# face_board.net
KiCad netlist of a schematic drawn in Altium Designer
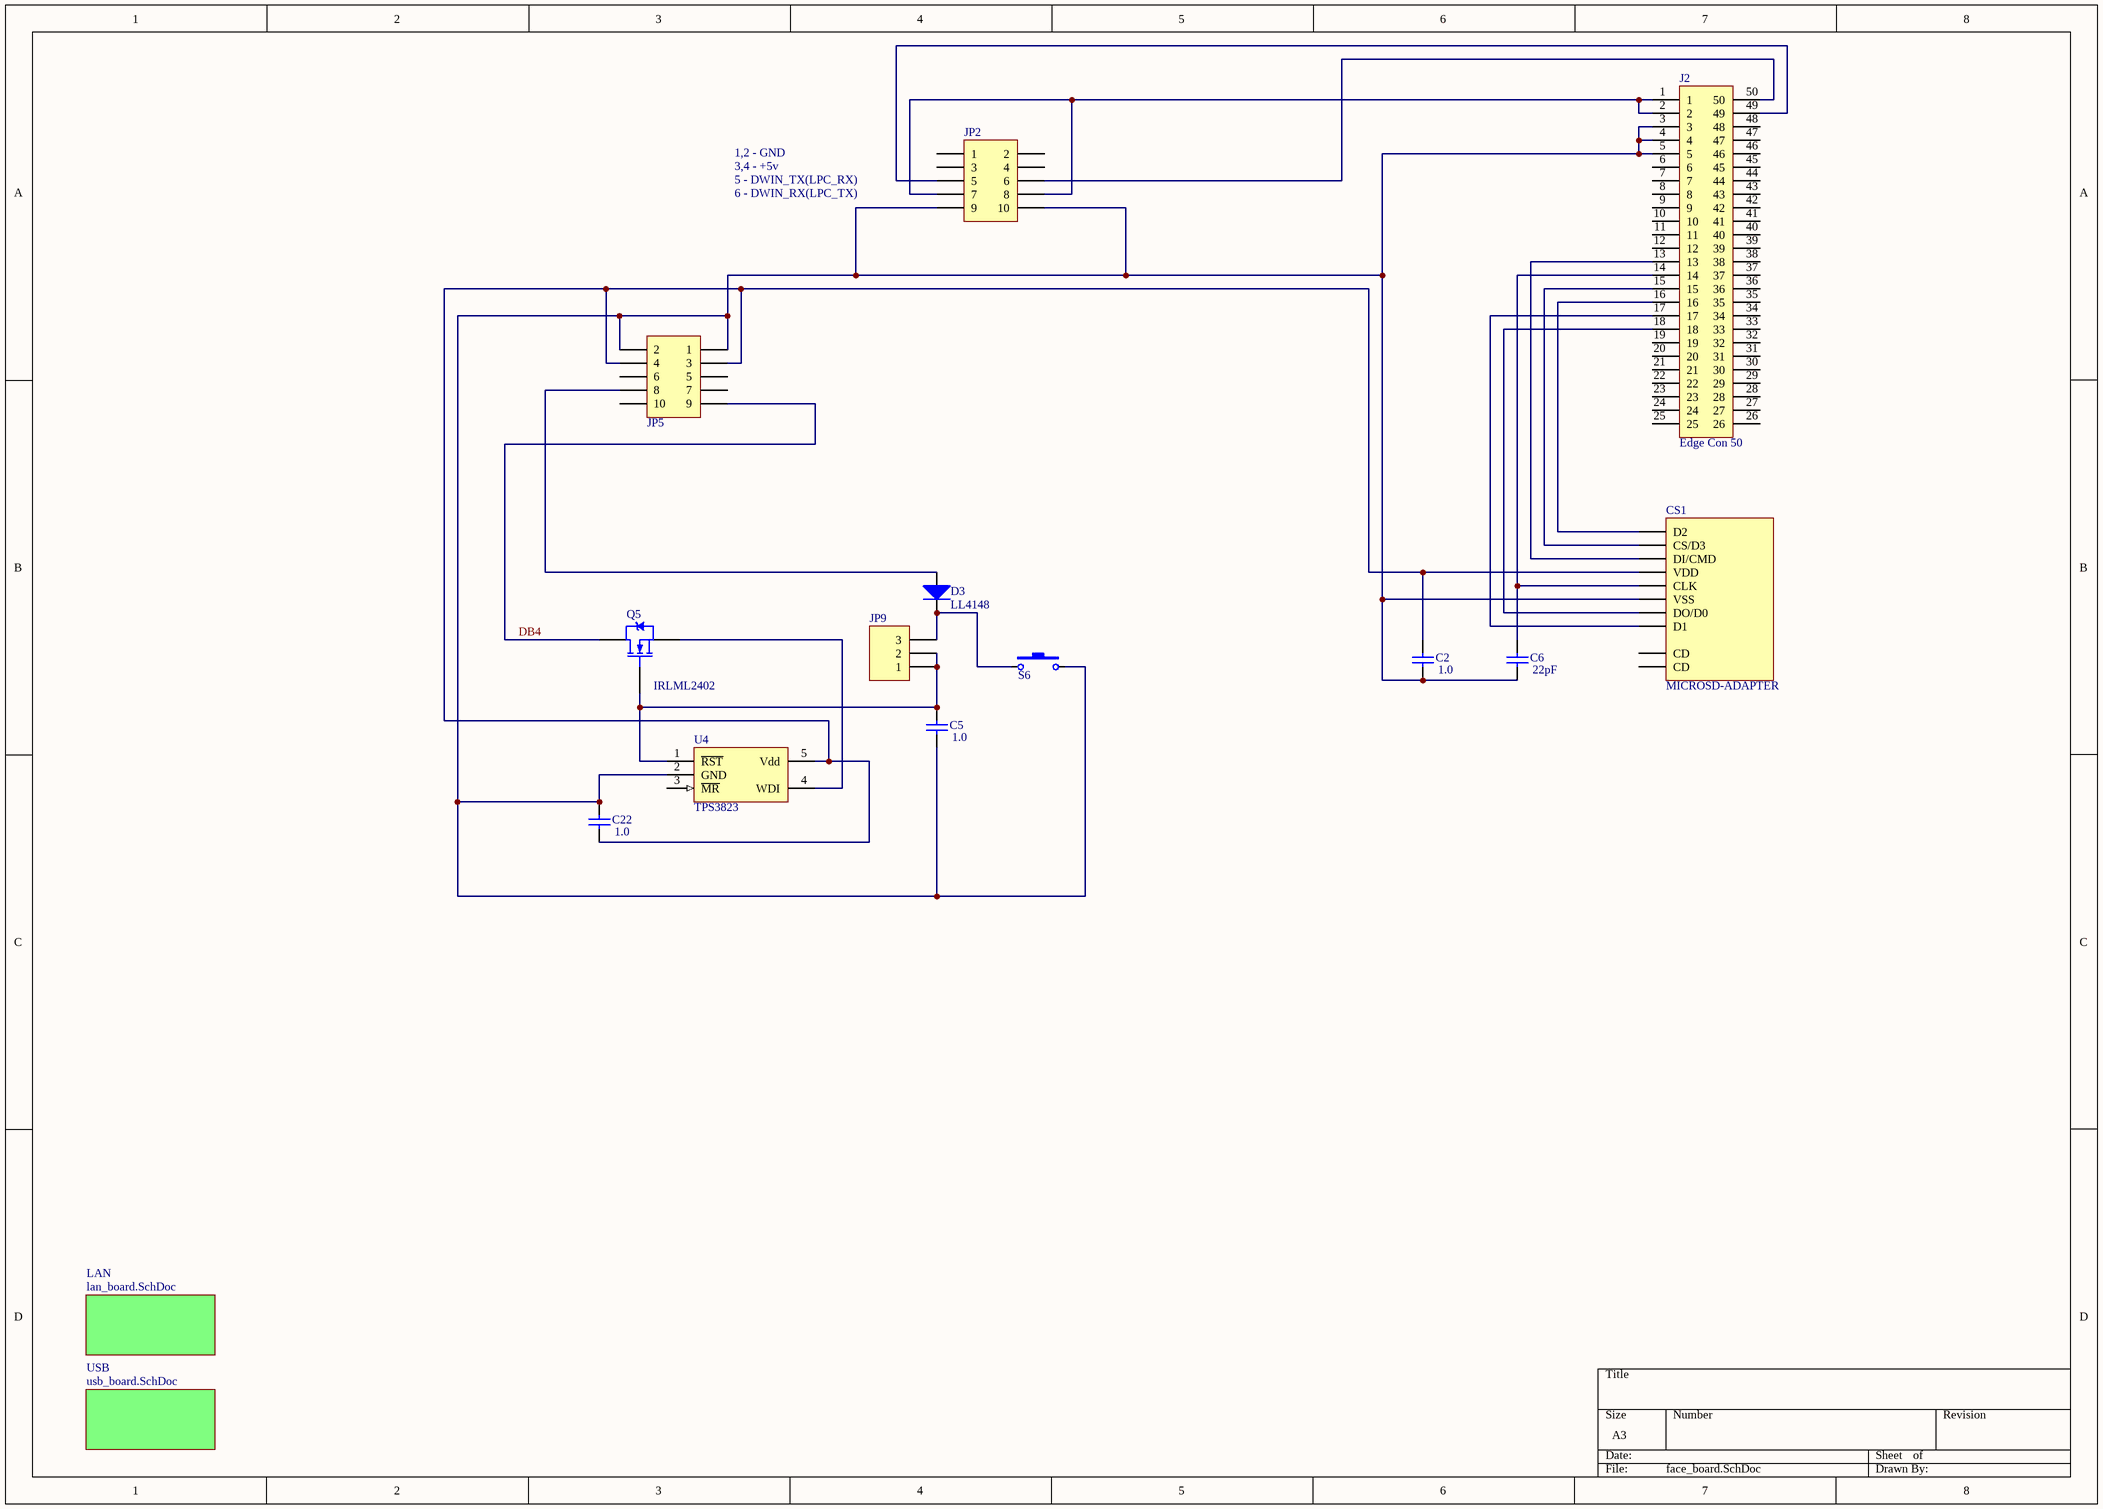
[diagram p0: face_board.SchDoc]

(export (version "E")
  (design (tool "Eeschema 10.0.6"))
  (components
    (comp (ref "C2")
      (value "1.0")
      (footprint "_0603")
      (description "Capacitor")
      (fields (field (name "MANUFACTURER") "Generic Components") (field (name "PUBLISHER") "Altium Limited"))
      (libsource (lib "Miscellaneous Devices") (part "Cap Semi"))
    )
    (comp (ref "C5")
      (value "1.0")
      (footprint "_0603")
      (description "Capacitor")
      (fields (field (name "MANUFACTURER") "Generic Components") (field (name "PUBLISHER") "Altium Limited"))
      (libsource (lib "Miscellaneous Devices") (part "Cap Semi"))
    )
    (comp (ref "C6")
      (value "22pF")
      (footprint "_0603")
      (description "Capacitor")
      (fields (field (name "MANUFACTURER") "Generic Components") (field (name "PUBLISHER") "Altium Limited"))
      (libsource (lib "Miscellaneous Devices") (part "Cap Semi"))
    )
    (comp (ref "C22")
      (value "1.0")
      (footprint "_0603")
      (description "Capacitor")
      (fields (field (name "MANUFACTURER") "Generic Components") (field (name "PUBLISHER") "Altium Limited"))
      (libsource (lib "Miscellaneous Devices") (part "Cap Semi"))
    )
    (comp (ref "CS1")
      (value "MICROSD-ADAPTER")
      (footprint "microsd_2")
      (libsource (lib "PAL") (part "MICROSD-ADAPTER"))
    )
    (comp (ref "D3")
      (value "LL4148")
      (footprint "_1206d")
      (description "Diode")
      (fields (field (name "MANUFACTURER") "Generic Components") (field (name "PUBLISHER") "Altium Limited"))
      (libsource (lib "PAL") (part "Diode"))
    )
    (comp (ref "J2")
      (value "Edge Con 50")
      (footprint "FH12-50")
      (description "50-Pin Edge Connector")
      (fields (field (name "MANUFACTURER") "Generic Components") (field (name "PUBLISHER") "Altium Limited"))
      (libsource (lib "Miscellaneous Connectors") (part "Edge Con 50"))
    )
    (comp (ref "JP2")
      (value "PBD-10")
      (footprint "HDR2X5")
      (description "Header, 5-Pin, Dual row")
      (fields (field (name "MANUFACTURER") "Generic Components") (field (name "PUBLISHER") "Altium Limited"))
      (libsource (lib "") (part "Header 5X2_1"))
    )
    (comp (ref "JP5")
      (value "PLHD-20")
      (footprint "HDR2X5")
      (description "Header, 5-Pin, Dual row")
      (fields (field (name "MANUFACTURER") "Generic Components") (field (name "PUBLISHER") "Altium Limited"))
      (libsource (lib "Miscellaneous Connectors") (part "Header 5X2"))
    )
    (comp (ref "JP9")
      (value "PLS-3")
      (footprint "HDR1X3")
      (description "Header, 3-Pin")
      (fields (field (name "MANUFACTURER") "Generic Components") (field (name "PUBLISHER") "Altium Limited"))
      (libsource (lib "Miscellaneous Connectors") (part "Header 3"))
    )
    (comp (ref "Q5")
      (value "IRLML2402")
      (footprint "SO-G3")
      (description "HEXFET Power MOSFET")
      (fields
        (field (name "MANUFACTURER") "International Rectifier")
        (field (name "ALTIUM_VALUE") "IRLML2402")
        (field (name "PUBLISHER") "Altium Limited")
      )
      (libsource (lib "IR Discrete MOSFET") (part "IRLML2402"))
    )
    (comp (ref "S6")
      (value "SWT-6")
      (footprint "SWT-6")
      (description "Button")
      (fields (field (name "MANUFACTURER") "Generic Components") (field (name "PUBLISHER") "Altium Limited"))
      (libsource (lib "PAL") (part "SWT-9"))
    )
    (comp (ref "U4")
      (value "TPS3823")
      (footprint "SO-G5/P.95")
      (description "Reset IC")
      (fields
        (field (name "MANUFACTURER") "National Semiconductor")
        (field (name "PUBLISHER") "Altium Limited")
      )
      (libsource (lib "PAL") (part "TPS3823"))
    )
  )
  (nets
    (net (code "1") (name "/DB4") (class "Default")
      (node (ref "JP5") (pin "9") (pinfunction "9_9") (pintype "passive"))
      (node (ref "Q5") (pin "3") (pinfunction "D_3") (pintype "passive"))
    )
    (net (code "2") (name "Net-(CS1-CLK)") (class "Default")
      (node (ref "C6") (pin "2") (pinfunction "2_2") (pintype "passive"))
      (node (ref "CS1") (pin "5") (pinfunction "CLK_5") (pintype "passive"))
      (node (ref "J2") (pin "14") (pinfunction "14_14") (pintype "passive"))
    )
    (net (code "3") (name "Net-(CS1-CS{slash}D3)") (class "Default")
      (node (ref "CS1") (pin "2") (pinfunction "CS/D3_2") (pintype "passive"))
      (node (ref "J2") (pin "15") (pinfunction "15_15") (pintype "passive"))
    )
    (net (code "4") (name "Net-(CS1-D1)") (class "Default")
      (node (ref "CS1") (pin "8") (pinfunction "D1_8") (pintype "passive"))
      (node (ref "J2") (pin "17") (pinfunction "17_17") (pintype "passive"))
    )
    (net (code "5") (name "Net-(CS1-D2)") (class "Default")
      (node (ref "CS1") (pin "1") (pinfunction "D2_1") (pintype "passive"))
      (node (ref "J2") (pin "16") (pinfunction "16_16") (pintype "passive"))
    )
    (net (code "6") (name "Net-(CS1-DI{slash}CMD)") (class "Default")
      (node (ref "CS1") (pin "3") (pinfunction "DI/CMD_3") (pintype "passive"))
      (node (ref "J2") (pin "13") (pinfunction "13_13") (pintype "passive"))
    )
    (net (code "7") (name "Net-(CS1-DO{slash}D0)") (class "Default")
      (node (ref "CS1") (pin "7") (pinfunction "DO/D0_7") (pintype "passive"))
      (node (ref "J2") (pin "18") (pinfunction "18_18") (pintype "passive"))
    )
    (net (code "8") (name "Net-(CS1-VDD)") (class "Default")
      (node (ref "C2") (pin "2") (pinfunction "2_2") (pintype "passive"))
      (node (ref "C22") (pin "1") (pinfunction "1_1") (pintype "passive"))
      (node (ref "CS1") (pin "4") (pinfunction "VDD_4") (pintype "passive"))
      (node (ref "JP5") (pin "3") (pinfunction "3_3") (pintype "passive"))
      (node (ref "JP5") (pin "4") (pinfunction "4_4") (pintype "passive"))
      (node (ref "U4") (pin "5") (pinfunction "Vdd_5") (pintype "power_in"))
    )
    (net (code "9") (name "Net-(CS1-VSS)") (class "Default")
      (node (ref "C2") (pin "1") (pinfunction "1_1") (pintype "passive"))
      (node (ref "C22") (pin "2") (pinfunction "2_2") (pintype "passive"))
      (node (ref "C5") (pin "1") (pinfunction "1_1") (pintype "passive"))
      (node (ref "C6") (pin "1") (pinfunction "1_1") (pintype "passive"))
      (node (ref "CS1") (pin "6") (pinfunction "VSS_6") (pintype "passive"))
      (node (ref "J2") (pin "3") (pinfunction "3_3") (pintype "passive"))
      (node (ref "J2") (pin "4") (pinfunction "4_4") (pintype "passive"))
      (node (ref "J2") (pin "5") (pinfunction "5_5") (pintype "passive"))
      (node (ref "JP2") (pin "10") (pinfunction "10_10") (pintype "passive"))
      (node (ref "JP2") (pin "9") (pinfunction "9_9") (pintype "passive"))
      (node (ref "JP5") (pin "1") (pinfunction "1_1") (pintype "passive"))
      (node (ref "JP5") (pin "2") (pinfunction "2_2") (pintype "passive"))
      (node (ref "S6") (pin "2") (pinfunction "2_2") (pintype "passive"))
      (node (ref "U4") (pin "2") (pinfunction "GND_2") (pintype "power_in"))
    )
    (net (code "10") (name "Net-(D3-A)") (class "Default")
      (node (ref "D3") (pin "1") (pinfunction "A_1") (pintype "passive"))
      (node (ref "JP5") (pin "8") (pinfunction "8_8") (pintype "passive"))
    )
    (net (code "11") (name "Net-(D3-K)") (class "Default")
      (node (ref "D3") (pin "2") (pinfunction "K_2") (pintype "passive"))
      (node (ref "JP9") (pin "3") (pinfunction "3_3") (pintype "passive"))
      (node (ref "S6") (pin "1") (pinfunction "1_1") (pintype "passive"))
    )
    (net (code "12") (name "Net-(J2-Pad1)") (class "Default")
      (node (ref "J2") (pin "1") (pinfunction "1_1") (pintype "passive"))
      (node (ref "J2") (pin "2") (pinfunction "2_2") (pintype "passive"))
      (node (ref "JP2") (pin "7") (pinfunction "7_7") (pintype "passive"))
      (node (ref "JP2") (pin "8") (pinfunction "8_8") (pintype "passive"))
    )
    (net (code "13") (name "Net-(J2-Pad49)") (class "Default")
      (node (ref "J2") (pin "49") (pinfunction "49_49") (pintype "passive"))
      (node (ref "JP2") (pin "5") (pinfunction "5_5") (pintype "passive"))
    )
    (net (code "14") (name "Net-(J2-Pad50)") (class "Default")
      (node (ref "J2") (pin "50") (pinfunction "50_50") (pintype "passive"))
      (node (ref "JP2") (pin "6") (pinfunction "6_6") (pintype "passive"))
    )
    (net (code "15") (name "Net-(Q5-G)") (class "Default")
      (node (ref "C5") (pin "2") (pinfunction "2_2") (pintype "passive"))
      (node (ref "JP9") (pin "1") (pinfunction "1_1") (pintype "passive"))
      (node (ref "JP9") (pin "2") (pinfunction "2_2") (pintype "passive"))
      (node (ref "Q5") (pin "1") (pinfunction "G_1") (pintype "passive"))
      (node (ref "U4") (pin "1") (pinfunction "~{RST}_1") (pintype "power_in"))
    )
    (net (code "16") (name "Net-(Q5-S)") (class "Default")
      (node (ref "Q5") (pin "2") (pinfunction "S_2") (pintype "passive"))
      (node (ref "U4") (pin "4") (pinfunction "WDI_4") (pintype "passive"))
    )
    (net (code "17") (name "unconnected-(CS1-CD-Pad9)") (class "Default")
      (node (ref "CS1") (pin "9") (pinfunction "CD_9") (pintype "passive"))
    )
    (net (code "18") (name "unconnected-(CS1-CD-Pad10)") (class "Default")
      (node (ref "CS1") (pin "10") (pinfunction "CD_10") (pintype "passive"))
    )
    (net (code "19") (name "unconnected-(J2-Pad6)") (class "Default")
      (node (ref "J2") (pin "6") (pinfunction "6_6") (pintype "passive"))
    )
    (net (code "20") (name "unconnected-(J2-Pad7)") (class "Default")
      (node (ref "J2") (pin "7") (pinfunction "7_7") (pintype "passive"))
    )
    (net (code "21") (name "unconnected-(J2-Pad8)") (class "Default")
      (node (ref "J2") (pin "8") (pinfunction "8_8") (pintype "passive"))
    )
    (net (code "22") (name "unconnected-(J2-Pad9)") (class "Default")
      (node (ref "J2") (pin "9") (pinfunction "9_9") (pintype "passive"))
    )
    (net (code "23") (name "unconnected-(J2-Pad10)") (class "Default")
      (node (ref "J2") (pin "10") (pinfunction "10_10") (pintype "passive"))
    )
    (net (code "24") (name "unconnected-(J2-Pad11)") (class "Default")
      (node (ref "J2") (pin "11") (pinfunction "11_11") (pintype "passive"))
    )
    (net (code "25") (name "unconnected-(J2-Pad12)") (class "Default")
      (node (ref "J2") (pin "12") (pinfunction "12_12") (pintype "passive"))
    )
    (net (code "26") (name "unconnected-(J2-Pad19)") (class "Default")
      (node (ref "J2") (pin "19") (pinfunction "19_19") (pintype "passive"))
    )
    (net (code "27") (name "unconnected-(J2-Pad20)") (class "Default")
      (node (ref "J2") (pin "20") (pinfunction "20_20") (pintype "passive"))
    )
    (net (code "28") (name "unconnected-(J2-Pad21)") (class "Default")
      (node (ref "J2") (pin "21") (pinfunction "21_21") (pintype "passive"))
    )
    (net (code "29") (name "unconnected-(J2-Pad22)") (class "Default")
      (node (ref "J2") (pin "22") (pinfunction "22_22") (pintype "passive"))
    )
    (net (code "30") (name "unconnected-(J2-Pad23)") (class "Default")
      (node (ref "J2") (pin "23") (pinfunction "23_23") (pintype "passive"))
    )
    (net (code "31") (name "unconnected-(J2-Pad24)") (class "Default")
      (node (ref "J2") (pin "24") (pinfunction "24_24") (pintype "passive"))
    )
    (net (code "32") (name "unconnected-(J2-Pad25)") (class "Default")
      (node (ref "J2") (pin "25") (pinfunction "25_25") (pintype "passive"))
    )
    (net (code "33") (name "unconnected-(J2-Pad26)") (class "Default")
      (node (ref "J2") (pin "26") (pinfunction "26_26") (pintype "passive"))
    )
    (net (code "34") (name "unconnected-(J2-Pad27)") (class "Default")
      (node (ref "J2") (pin "27") (pinfunction "27_27") (pintype "passive"))
    )
    (net (code "35") (name "unconnected-(J2-Pad28)") (class "Default")
      (node (ref "J2") (pin "28") (pinfunction "28_28") (pintype "passive"))
    )
    (net (code "36") (name "unconnected-(J2-Pad29)") (class "Default")
      (node (ref "J2") (pin "29") (pinfunction "29_29") (pintype "passive"))
    )
    (net (code "37") (name "unconnected-(J2-Pad30)") (class "Default")
      (node (ref "J2") (pin "30") (pinfunction "30_30") (pintype "passive"))
    )
    (net (code "38") (name "unconnected-(J2-Pad31)") (class "Default")
      (node (ref "J2") (pin "31") (pinfunction "31_31") (pintype "passive"))
    )
    (net (code "39") (name "unconnected-(J2-Pad32)") (class "Default")
      (node (ref "J2") (pin "32") (pinfunction "32_32") (pintype "passive"))
    )
    (net (code "40") (name "unconnected-(J2-Pad33)") (class "Default")
      (node (ref "J2") (pin "33") (pinfunction "33_33") (pintype "passive"))
    )
    (net (code "41") (name "unconnected-(J2-Pad34)") (class "Default")
      (node (ref "J2") (pin "34") (pinfunction "34_34") (pintype "passive"))
    )
    (net (code "42") (name "unconnected-(J2-Pad35)") (class "Default")
      (node (ref "J2") (pin "35") (pinfunction "35_35") (pintype "passive"))
    )
    (net (code "43") (name "unconnected-(J2-Pad36)") (class "Default")
      (node (ref "J2") (pin "36") (pinfunction "36_36") (pintype "passive"))
    )
    (net (code "44") (name "unconnected-(J2-Pad37)") (class "Default")
      (node (ref "J2") (pin "37") (pinfunction "37_37") (pintype "passive"))
    )
    (net (code "45") (name "unconnected-(J2-Pad38)") (class "Default")
      (node (ref "J2") (pin "38") (pinfunction "38_38") (pintype "passive"))
    )
    (net (code "46") (name "unconnected-(J2-Pad39)") (class "Default")
      (node (ref "J2") (pin "39") (pinfunction "39_39") (pintype "passive"))
    )
    (net (code "47") (name "unconnected-(J2-Pad40)") (class "Default")
      (node (ref "J2") (pin "40") (pinfunction "40_40") (pintype "passive"))
    )
    (net (code "48") (name "unconnected-(J2-Pad41)") (class "Default")
      (node (ref "J2") (pin "41") (pinfunction "41_41") (pintype "passive"))
    )
    (net (code "49") (name "unconnected-(J2-Pad42)") (class "Default")
      (node (ref "J2") (pin "42") (pinfunction "42_42") (pintype "passive"))
    )
    (net (code "50") (name "unconnected-(J2-Pad43)") (class "Default")
      (node (ref "J2") (pin "43") (pinfunction "43_43") (pintype "passive"))
    )
    (net (code "51") (name "unconnected-(J2-Pad44)") (class "Default")
      (node (ref "J2") (pin "44") (pinfunction "44_44") (pintype "passive"))
    )
    (net (code "52") (name "unconnected-(J2-Pad45)") (class "Default")
      (node (ref "J2") (pin "45") (pinfunction "45_45") (pintype "passive"))
    )
    (net (code "53") (name "unconnected-(J2-Pad46)") (class "Default")
      (node (ref "J2") (pin "46") (pinfunction "46_46") (pintype "passive"))
    )
    (net (code "54") (name "unconnected-(J2-Pad47)") (class "Default")
      (node (ref "J2") (pin "47") (pinfunction "47_47") (pintype "passive"))
    )
    (net (code "55") (name "unconnected-(J2-Pad48)") (class "Default")
      (node (ref "J2") (pin "48") (pinfunction "48_48") (pintype "passive"))
    )
    (net (code "56") (name "unconnected-(JP2-Pad1)") (class "Default")
      (node (ref "JP2") (pin "1") (pinfunction "1_1") (pintype "passive"))
    )
    (net (code "57") (name "unconnected-(JP2-Pad2)") (class "Default")
      (node (ref "JP2") (pin "2") (pinfunction "2_2") (pintype "passive"))
    )
    (net (code "58") (name "unconnected-(JP2-Pad3)") (class "Default")
      (node (ref "JP2") (pin "3") (pinfunction "3_3") (pintype "passive"))
    )
    (net (code "59") (name "unconnected-(JP2-Pad4)") (class "Default")
      (node (ref "JP2") (pin "4") (pinfunction "4_4") (pintype "passive"))
    )
    (net (code "60") (name "unconnected-(JP5-Pad5)") (class "Default")
      (node (ref "JP5") (pin "5") (pinfunction "5_5") (pintype "passive"))
    )
    (net (code "61") (name "unconnected-(JP5-Pad6)") (class "Default")
      (node (ref "JP5") (pin "6") (pinfunction "6_6") (pintype "passive"))
    )
    (net (code "62") (name "unconnected-(JP5-Pad7)") (class "Default")
      (node (ref "JP5") (pin "7") (pinfunction "7_7") (pintype "passive"))
    )
    (net (code "63") (name "unconnected-(JP5-Pad10)") (class "Default")
      (node (ref "JP5") (pin "10") (pinfunction "10_10") (pintype "passive"))
    )
    (net (code "64") (name "unconnected-(U4-~{MR}-Pad3)") (class "Default")
      (node (ref "U4") (pin "3") (pinfunction "~{MR}_3") (pintype "input"))
    )
  )
)
